# NinjaPCB_ver2_2.net
KiCad netlist of a schematic drawn in EAGLE
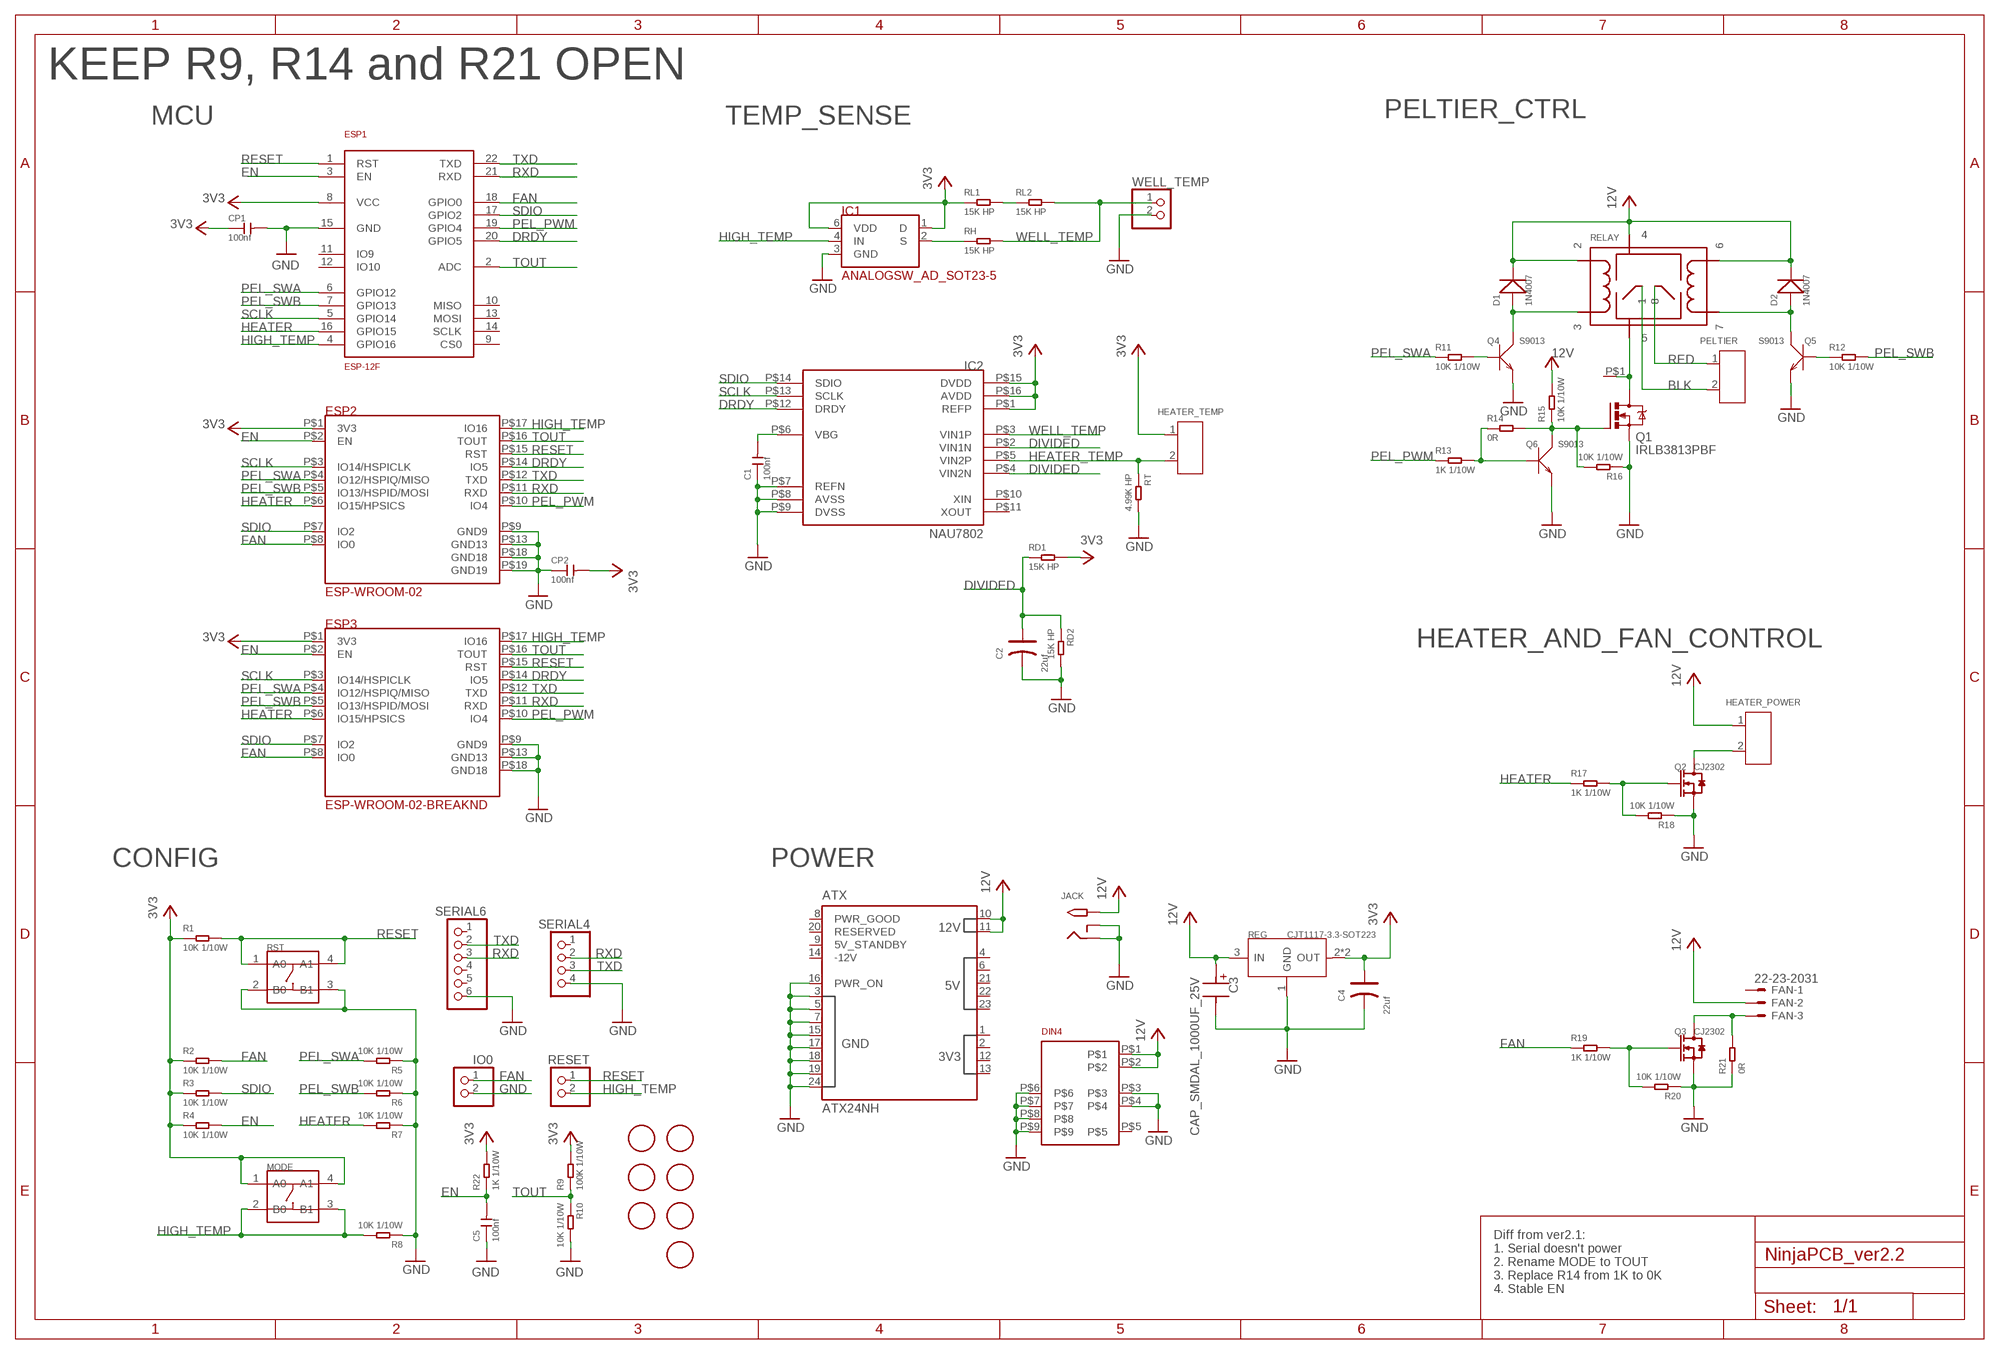
[diagram p0: schematic, sheet 1]

(export (version "E")
  (design (tool "Eeschema 10.0.6"))
  (components
    (comp (ref "ATX")
      (value "ATX24NH")
      (footprint "eagle-import:ATX24")
      (libsource (lib "eagle-import") (part "ATX24NH"))
    )
    (comp (ref "C1")
      (value "100nf")
      (footprint "eagle-import:C0603")
      (fields (field (name "MPN") "CC0603KRX7R9BB104"))
      (libsource (lib "eagle-import") (part "CERAMIC-100NF-50V-10%-X7R(0603)"))
    )
    (comp (ref "C2")
      (value "22uf")
      (footprint "eagle-import:AVX-B")
      (fields (field (name "MPN") "TAJB226*016#NJ"))
      (libsource (lib "eagle-import") (part "TANTALUM-SMD-22UF-16V(AVX-B)"))
    )
    (comp (ref "C3")
      (value "CAP_SMDAL_1000UF_25V")
      (footprint "eagle-import:CAP_SMD_AL_D125")
      (libsource (lib "eagle-import") (part "CAP_SMDAL_1000UF_25V"))
    )
    (comp (ref "C4")
      (value "22uf")
      (footprint "eagle-import:AVX-B")
      (fields (field (name "MPN") "TAJB226*016#NJ"))
      (libsource (lib "eagle-import") (part "TANTALUM-SMD-22UF-16V(AVX-B)"))
    )
    (comp (ref "C5")
      (value "100nf")
      (footprint "eagle-import:C0603")
      (fields (field (name "MPN") "CC0603KRX7R9BB104"))
      (libsource (lib "eagle-import") (part "CERAMIC-100NF-50V-10%-X7R(0603)"))
    )
    (comp (ref "CP1")
      (value "100nf")
      (footprint "eagle-import:C0603")
      (fields (field (name "MPN") "CC0603KRX7R9BB104"))
      (libsource (lib "eagle-import") (part "CERAMIC-100NF-50V-10%-X7R(0603)"))
    )
    (comp (ref "CP2")
      (value "100nf")
      (footprint "eagle-import:C0603")
      (fields (field (name "MPN") "CC0603KRX7R9BB104"))
      (libsource (lib "eagle-import") (part "CERAMIC-100NF-50V-10%-X7R(0603)"))
    )
    (comp (ref "D1")
      (value "1N4007")
      (footprint "eagle-import:DO-214AC")
      (libsource (lib "eagle-import") (part "DIODE-GEN-PURPOSE-1KV-1A(DO-214AC)"))
    )
    (comp (ref "D2")
      (value "1N4007")
      (footprint "eagle-import:DO-214AC")
      (libsource (lib "eagle-import") (part "DIODE-GEN-PURPOSE-1KV-1A(DO-214AC)"))
    )
    (comp (ref "DIN4")
      (value "DIN4")
      (footprint "eagle-import:DIN4")
      (libsource (lib "eagle-import") (part "DIN4"))
    )
    (comp (ref "ESP1")
      (value "ESP-12F")
      (footprint "eagle-import:ESP-12F")
      (libsource (lib "eagle-import") (part "ESP-12F"))
    )
    (comp (ref "ESP2")
      (value "ESP-WROOM-02")
      (footprint "eagle-import:ESP-WROOM-02")
      (libsource (lib "eagle-import") (part "ESP-WROOM-02"))
    )
    (comp (ref "ESP3")
      (value "ESP-WROOM-02-BREAKND")
      (footprint "eagle-import:ESP-WROOM-02-BREAK-NODETAIL")
      (libsource (lib "eagle-import") (part "ESP-WROOM-02-BREAKND"))
    )
    (comp (ref "FAN")
      (value "22-23-2031")
      (footprint "eagle-import:22-23-2031")
      (fields (field (name "MF") "MOLEX"))
      (libsource (lib "eagle-import") (part "22-23-2031"))
    )
    (comp (ref "HEATER_POWER")
      (value "SCREW-TERMINAL-GREEN(2P-3.5)")
      (footprint "eagle-import:H2-3.5-7.0X7.0MM")
      (libsource (lib "eagle-import") (part "SCREW-TERMINAL-GREEN(2P-3.5)"))
    )
    (comp (ref "HEATER_TEMP")
      (value "SCREW-TERMINAL-GREEN(2P-3.5)")
      (footprint "eagle-import:H2-3.5-7.0X7.0MM")
      (libsource (lib "eagle-import") (part "SCREW-TERMINAL-GREEN(2P-3.5)"))
    )
    (comp (ref "HEATSINK")
      (value "HEAT111PB015")
      (footprint "eagle-import:HEAT11PB015")
      (libsource (lib "eagle-import") (part "HEAT111PB015"))
    )
    (comp (ref "IC1")
      (value "ANALOGSW_AD_SOT23-5")
      (footprint "eagle-import:SOT23-5")
      (libsource (lib "eagle-import") (part "ANALOGSW_AD_SOT23-5"))
    )
    (comp (ref "IC2")
      (value "NAU7802")
      (footprint "eagle-import:SOP-16")
      (libsource (lib "eagle-import") (part "NAU7802"))
    )
    (comp (ref "IO0")
      (value "PINHD-1X2")
      (footprint "eagle-import:1X02")
      (libsource (lib "eagle-import") (part "PINHD-1X2"))
    )
    (comp (ref "JACK")
      (value "2.1MMJACKTHM-NOOUT")
      (footprint "eagle-import:PJ-102A-NOOUT")
      (libsource (lib "eagle-import") (part "2.1MMJACKTHM-NOOUT"))
    )
    (comp (ref "MODE")
      (value "DIP-SWITCH-TACTILE-SPST-NO/TS-1109(4P-D6.0MM)'TS-1109'")
      (footprint "eagle-import:SW4-6.0X6.0X5.0MM")
      (libsource (lib "eagle-import") (part "DIP-SWITCH-TACTILE-SPST-NO/TS-1109(4P-D6.0MM)'TS-1109'"))
    )
    (comp (ref "PELTIER")
      (value "SCREW-TERMINAL-GREEN(2P-3.5)")
      (footprint "eagle-import:H2-3.5-7.0X7.0MM")
      (libsource (lib "eagle-import") (part "SCREW-TERMINAL-GREEN(2P-3.5)"))
    )
    (comp (ref "Q1")
      (value "IRLB3813PBF")
      (footprint "eagle-import:TO220BV")
      (libsource (lib "eagle-import") (part "IRF520"))
    )
    (comp (ref "Q2")
      (value "CJ2302")
      (footprint "eagle-import:SOT-23")
      (libsource (lib "eagle-import") (part "SMD-MOSFET-N-CH-20V-2.1A-CJ2302(SOT-23)"))
    )
    (comp (ref "Q3")
      (value "CJ2302")
      (footprint "eagle-import:SOT-23")
      (libsource (lib "eagle-import") (part "SMD-MOSFET-N-CH-20V-2.1A-CJ2302(SOT-23)"))
    )
    (comp (ref "Q4")
      (value "S9013")
      (footprint "eagle-import:SOT-23")
      (libsource (lib "eagle-import") (part "SMD-TRANSISTORS-NPN-25V-500MA-S9013(SOT-23)"))
    )
    (comp (ref "Q5")
      (value "S9013")
      (footprint "eagle-import:SOT-23")
      (libsource (lib "eagle-import") (part "SMD-TRANSISTORS-NPN-25V-500MA-S9013(SOT-23)"))
    )
    (comp (ref "Q6")
      (value "S9013")
      (footprint "eagle-import:SOT-23")
      (libsource (lib "eagle-import") (part "SMD-TRANSISTORS-NPN-25V-500MA-S9013(SOT-23)"))
    )
    (comp (ref "R1")
      (value "10K 1/10W")
      (footprint "eagle-import:R0603")
      (fields (field (name "MPN") "RC0603JR-0710KL"))
      (libsource (lib "eagle-import") (part "SMD-RES-10K-5%-1/10W(0603)"))
    )
    (comp (ref "R2")
      (value "10K 1/10W")
      (footprint "eagle-import:R0603")
      (fields (field (name "MPN") "RC0603JR-0710KL"))
      (libsource (lib "eagle-import") (part "SMD-RES-10K-5%-1/10W(0603)"))
    )
    (comp (ref "R3")
      (value "10K 1/10W")
      (footprint "eagle-import:R0603")
      (fields (field (name "MPN") "RC0603JR-0710KL"))
      (libsource (lib "eagle-import") (part "SMD-RES-10K-5%-1/10W(0603)"))
    )
    (comp (ref "R4")
      (value "10K 1/10W")
      (footprint "eagle-import:R0603")
      (fields (field (name "MPN") "RC0603JR-0710KL"))
      (libsource (lib "eagle-import") (part "SMD-RES-10K-5%-1/10W(0603)"))
    )
    (comp (ref "R5")
      (value "10K 1/10W")
      (footprint "eagle-import:R0603")
      (fields (field (name "MPN") "RC0603JR-0710KL"))
      (libsource (lib "eagle-import") (part "SMD-RES-10K-5%-1/10W(0603)"))
    )
    (comp (ref "R6")
      (value "10K 1/10W")
      (footprint "eagle-import:R0603")
      (fields (field (name "MPN") "RC0603JR-0710KL"))
      (libsource (lib "eagle-import") (part "SMD-RES-10K-5%-1/10W(0603)"))
    )
    (comp (ref "R7")
      (value "10K 1/10W")
      (footprint "eagle-import:R0603")
      (fields (field (name "MPN") "RC0603JR-0710KL"))
      (libsource (lib "eagle-import") (part "SMD-RES-10K-5%-1/10W(0603)"))
    )
    (comp (ref "R8")
      (value "10K 1/10W")
      (footprint "eagle-import:R0603")
      (fields (field (name "MPN") "RC0603JR-0710KL"))
      (libsource (lib "eagle-import") (part "SMD-RES-10K-5%-1/10W(0603)"))
    )
    (comp (ref "R9")
      (value "100K 1/10W")
      (footprint "eagle-import:R0603")
      (fields (field (name "MPN") "RC0603JR-07100KL"))
      (libsource (lib "eagle-import") (part "SMD-RES-100K-5%-1/10W(0603)"))
    )
    (comp (ref "R10")
      (value "10K 1/10W")
      (footprint "eagle-import:R0603")
      (fields (field (name "MPN") "RC0603JR-0710KL"))
      (libsource (lib "eagle-import") (part "SMD-RES-10K-5%-1/10W(0603)"))
    )
    (comp (ref "R11")
      (value "10K 1/10W")
      (footprint "eagle-import:R0603")
      (fields (field (name "MPN") "RC0603JR-0710KL"))
      (libsource (lib "eagle-import") (part "SMD-RES-10K-5%-1/10W(0603)"))
    )
    (comp (ref "R12")
      (value "10K 1/10W")
      (footprint "eagle-import:R0603")
      (fields (field (name "MPN") "RC0603JR-0710KL"))
      (libsource (lib "eagle-import") (part "SMD-RES-10K-5%-1/10W(0603)"))
    )
    (comp (ref "R13")
      (value "1K 1/10W")
      (footprint "eagle-import:R0603")
      (fields (field (name "MPN") "RC0603JR-071KL"))
      (libsource (lib "eagle-import") (part "SMD-RES-1K-5%-1/10W(0603)"))
    )
    (comp (ref "R14")
      (value "0R")
      (footprint "eagle-import:R0603")
      (fields (field (name "MPN") "RC0603JR-070RL"))
      (libsource (lib "eagle-import") (part "SMD-RES-0R-5%-1/10W(0603)"))
    )
    (comp (ref "R15")
      (value "10K 1/10W")
      (footprint "eagle-import:R0603")
      (fields (field (name "MPN") "RC0603JR-0710KL"))
      (libsource (lib "eagle-import") (part "SMD-RES-10K-5%-1/10W(0603)"))
    )
    (comp (ref "R16")
      (value "10K 1/10W")
      (footprint "eagle-import:R0603")
      (fields (field (name "MPN") "RC0603JR-0710KL"))
      (libsource (lib "eagle-import") (part "SMD-RES-10K-5%-1/10W(0603)"))
    )
    (comp (ref "R17")
      (value "1K 1/10W")
      (footprint "eagle-import:R0603")
      (fields (field (name "MPN") "RC0603JR-071KL"))
      (libsource (lib "eagle-import") (part "SMD-RES-1K-5%-1/10W(0603)"))
    )
    (comp (ref "R18")
      (value "10K 1/10W")
      (footprint "eagle-import:R0603")
      (fields (field (name "MPN") "RC0603JR-0710KL"))
      (libsource (lib "eagle-import") (part "SMD-RES-10K-5%-1/10W(0603)"))
    )
    (comp (ref "R19")
      (value "1K 1/10W")
      (footprint "eagle-import:R0603")
      (fields (field (name "MPN") "RC0603JR-071KL"))
      (libsource (lib "eagle-import") (part "SMD-RES-1K-5%-1/10W(0603)"))
    )
    (comp (ref "R20")
      (value "10K 1/10W")
      (footprint "eagle-import:R0603")
      (fields (field (name "MPN") "RC0603JR-0710KL"))
      (libsource (lib "eagle-import") (part "SMD-RES-10K-5%-1/10W(0603)"))
    )
    (comp (ref "R21")
      (value "0R")
      (footprint "eagle-import:R0603")
      (fields (field (name "MPN") "RC0603JR-070RL"))
      (libsource (lib "eagle-import") (part "SMD-RES-0R-5%-1/10W(0603)"))
    )
    (comp (ref "R22")
      (value "1K 1/10W")
      (footprint "eagle-import:R0603")
      (fields (field (name "MPN") "RC0603JR-071KL"))
      (libsource (lib "eagle-import") (part "SMD-RES-1K-5%-1/10W(0603)"))
    )
    (comp (ref "RD1")
      (value "15K HP")
      (footprint "eagle-import:R0603")
      (libsource (lib "eagle-import") (part "R0603"))
    )
    (comp (ref "RD2")
      (value "15K HP")
      (footprint "eagle-import:R0603")
      (libsource (lib "eagle-import") (part "R0603"))
    )
    (comp (ref "REG")
      (value "CJT1117-3.3-SOT223")
      (footprint "eagle-import:SOT-223")
      (fields (field (name "MPN") "CJT1117-3.3"))
      (libsource (lib "eagle-import") (part "PMIC-CJT1117-3.3(SOT223)"))
    )
    (comp (ref "RELAY")
      (value "NEC-RELAY2EP2")
      (footprint "eagle-import:NEC-EP2")
      (libsource (lib "eagle-import") (part "NEC-RELAY2EP2"))
    )
    (comp (ref "RESET")
      (value "PINHD-1X2")
      (footprint "eagle-import:1X02")
      (libsource (lib "eagle-import") (part "PINHD-1X2"))
    )
    (comp (ref "RH")
      (value "15K HP")
      (footprint "eagle-import:R0603")
      (libsource (lib "eagle-import") (part "R0603"))
    )
    (comp (ref "RL1")
      (value "15K HP")
      (footprint "eagle-import:R0603")
      (libsource (lib "eagle-import") (part "R0603"))
    )
    (comp (ref "RL2")
      (value "15K HP")
      (footprint "eagle-import:R0603")
      (libsource (lib "eagle-import") (part "R0603"))
    )
    (comp (ref "RST")
      (value "DIP-SWITCH-TACTILE-SPST-NO/TS-1109(4P-D6.0MM)'TS-1109'")
      (footprint "eagle-import:SW4-6.0X6.0X5.0MM")
      (libsource (lib "eagle-import") (part "DIP-SWITCH-TACTILE-SPST-NO/TS-1109(4P-D6.0MM)'TS-1109'"))
    )
    (comp (ref "RT")
      (value "4.99K HP")
      (footprint "eagle-import:R0603")
      (fields (field (name "MPN") "RC0603FR-072KL"))
      (libsource (lib "eagle-import") (part "SMD-RES-2K-1%-1/10W(0603)"))
    )
    (comp (ref "SERIAL4")
      (value "PINHD-1X4")
      (footprint "eagle-import:1X04")
      (libsource (lib "eagle-import") (part "PINHD-1X4"))
    )
    (comp (ref "SERIAL6")
      (value "PINHD-1X6")
      (footprint "eagle-import:1X06")
      (libsource (lib "eagle-import") (part "PINHD-1X6"))
    )
    (comp (ref "U$3")
      (value "FIDUCIAL")
      (footprint "eagle-import:FIDUCIAL_1MM")
      (libsource (lib "eagle-import") (part "FIDUCIAL"))
    )
    (comp (ref "U$4")
      (value "FIDUCIAL")
      (footprint "eagle-import:FIDUCIAL_1MM")
      (libsource (lib "eagle-import") (part "FIDUCIAL"))
    )
    (comp (ref "U$5")
      (value "FIDUCIAL")
      (footprint "eagle-import:FIDUCIAL_1MM")
      (libsource (lib "eagle-import") (part "FIDUCIAL"))
    )
    (comp (ref "U$7")
      (value "FIDUCIAL")
      (footprint "eagle-import:FIDUCIAL_1MM")
      (libsource (lib "eagle-import") (part "FIDUCIAL"))
    )
    (comp (ref "U$8")
      (value "FIDUCIAL")
      (footprint "eagle-import:FIDUCIAL_1MM")
      (libsource (lib "eagle-import") (part "FIDUCIAL"))
    )
    (comp (ref "U$9")
      (value "FIDUCIAL")
      (footprint "eagle-import:FIDUCIAL_1MM")
      (libsource (lib "eagle-import") (part "FIDUCIAL"))
    )
    (comp (ref "U$10")
      (value "FIDUCIAL")
      (footprint "eagle-import:FIDUCIAL_1MM")
      (libsource (lib "eagle-import") (part "FIDUCIAL"))
    )
    (comp (ref "WELL_TEMP")
      (value "PINHD-1X2/90")
      (footprint "eagle-import:1X02_90")
      (libsource (lib "eagle-import") (part "PINHD-1X2/90"))
    )
  )
  (nets
    (net (code "1") (name "/BLK") (class "Default")
      (node (ref "PELTIER") (pin "2") (pinfunction "2_2") (pintype "bidirectional"))
      (node (ref "RELAY") (pin "P$1") (pinfunction "1_P$1") (pintype "bidirectional"))
    )
    (net (code "2") (name "/DIVIDED") (class "Default")
      (node (ref "C2") (pin "+") (pinfunction "+_+") (pintype "passive"))
      (node (ref "IC2") (pin "P$2") (pinfunction "VIN1N_P$2") (pintype "bidirectional"))
      (node (ref "IC2") (pin "P$4") (pinfunction "VIN2N_P$4") (pintype "bidirectional"))
      (node (ref "RD1") (pin "1") (pinfunction "1_1") (pintype "passive"))
      (node (ref "RD2") (pin "1") (pinfunction "1_1") (pintype "passive"))
    )
    (net (code "3") (name "/DRDY") (class "Default")
      (node (ref "ESP1") (pin "20") (pinfunction "GPIO5_20") (pintype "bidirectional"))
      (node (ref "ESP2") (pin "P$14") (pinfunction "IO5_P$14") (pintype "bidirectional"))
      (node (ref "ESP3") (pin "P$14") (pinfunction "IO5_P$14") (pintype "bidirectional"))
      (node (ref "IC2") (pin "P$12") (pinfunction "DRDY_P$12") (pintype "bidirectional"))
    )
    (net (code "4") (name "/EN") (class "Default")
      (node (ref "C5") (pin "2") (pinfunction "2_2") (pintype "passive"))
      (node (ref "ESP1") (pin "3") (pinfunction "EN_3") (pintype "bidirectional"))
      (node (ref "ESP2") (pin "P$2") (pinfunction "EN_P$2") (pintype "bidirectional"))
      (node (ref "ESP3") (pin "P$2") (pinfunction "EN_P$2") (pintype "bidirectional"))
      (node (ref "R22") (pin "1") (pinfunction "1_1") (pintype "passive"))
      (node (ref "R4") (pin "2") (pinfunction "2_2") (pintype "passive"))
    )
    (net (code "5") (name "/FAN") (class "Default")
      (node (ref "ESP1") (pin "18") (pinfunction "GPIO0_18") (pintype "bidirectional"))
      (node (ref "ESP2") (pin "P$8") (pinfunction "IO0_P$8") (pintype "bidirectional"))
      (node (ref "ESP3") (pin "P$8") (pinfunction "IO0_P$8") (pintype "bidirectional"))
      (node (ref "IO0") (pin "1") (pinfunction "1_1") (pintype "passive"))
      (node (ref "R19") (pin "1") (pinfunction "1_1") (pintype "passive"))
      (node (ref "R2") (pin "2") (pinfunction "2_2") (pintype "passive"))
    )
    (net (code "6") (name "/HEATER") (class "Default")
      (node (ref "ESP1") (pin "16") (pinfunction "GPIO15_16") (pintype "bidirectional"))
      (node (ref "ESP2") (pin "P$6") (pinfunction "IO15/HPSICS_P$6") (pintype "bidirectional"))
      (node (ref "ESP3") (pin "P$6") (pinfunction "IO15/HPSICS_P$6") (pintype "bidirectional"))
      (node (ref "R17") (pin "1") (pinfunction "1_1") (pintype "passive"))
      (node (ref "R7") (pin "2") (pinfunction "2_2") (pintype "passive"))
    )
    (net (code "7") (name "/HEATER_TEMP") (class "Default")
      (node (ref "HEATER_TEMP") (pin "2") (pinfunction "2_2") (pintype "bidirectional"))
      (node (ref "IC2") (pin "P$5") (pinfunction "VIN2P_P$5") (pintype "bidirectional"))
      (node (ref "RT") (pin "1") (pinfunction "1_1") (pintype "passive"))
    )
    (net (code "8") (name "/HIGH_TEMP") (class "Default")
      (node (ref "ESP1") (pin "4") (pinfunction "GPIO16_4") (pintype "bidirectional"))
      (node (ref "ESP2") (pin "P$17") (pinfunction "IO16_P$17") (pintype "bidirectional"))
      (node (ref "ESP3") (pin "P$17") (pinfunction "IO16_P$17") (pintype "bidirectional"))
      (node (ref "IC1") (pin "4") (pinfunction "IN_4") (pintype "bidirectional"))
      (node (ref "MODE") (pin "2") (pinfunction "B0_2") (pintype "bidirectional"))
      (node (ref "MODE") (pin "3") (pinfunction "B1_3") (pintype "bidirectional"))
      (node (ref "R8") (pin "2") (pinfunction "2_2") (pintype "passive"))
      (node (ref "RESET") (pin "2") (pinfunction "2_2") (pintype "passive"))
    )
    (net (code "9") (name "/PEL_PWM") (class "Default")
      (node (ref "ESP1") (pin "19") (pinfunction "GPIO4_19") (pintype "bidirectional"))
      (node (ref "ESP2") (pin "P$10") (pinfunction "IO4_P$10") (pintype "bidirectional"))
      (node (ref "ESP3") (pin "P$10") (pinfunction "IO4_P$10") (pintype "bidirectional"))
      (node (ref "R13") (pin "1") (pinfunction "1_1") (pintype "passive"))
    )
    (net (code "10") (name "/PEL_SWA") (class "Default")
      (node (ref "ESP1") (pin "6") (pinfunction "GPIO12_6") (pintype "bidirectional"))
      (node (ref "ESP2") (pin "P$4") (pinfunction "IO12/HSPIQ/MISO_P$4") (pintype "bidirectional"))
      (node (ref "ESP3") (pin "P$4") (pinfunction "IO12/HSPIQ/MISO_P$4") (pintype "bidirectional"))
      (node (ref "R11") (pin "1") (pinfunction "1_1") (pintype "passive"))
      (node (ref "R5") (pin "2") (pinfunction "2_2") (pintype "passive"))
    )
    (net (code "11") (name "/PEL_SWB") (class "Default")
      (node (ref "ESP1") (pin "7") (pinfunction "GPIO13_7") (pintype "bidirectional"))
      (node (ref "ESP2") (pin "P$5") (pinfunction "IO13/HSPID/MOSI_P$5") (pintype "bidirectional"))
      (node (ref "ESP3") (pin "P$5") (pinfunction "IO13/HSPID/MOSI_P$5") (pintype "bidirectional"))
      (node (ref "R12") (pin "2") (pinfunction "2_2") (pintype "passive"))
      (node (ref "R6") (pin "2") (pinfunction "2_2") (pintype "passive"))
    )
    (net (code "12") (name "/RED") (class "Default")
      (node (ref "PELTIER") (pin "1") (pinfunction "1_1") (pintype "bidirectional"))
      (node (ref "RELAY") (pin "P$8") (pinfunction "8_P$8") (pintype "bidirectional"))
    )
    (net (code "13") (name "/RESET") (class "Default")
      (node (ref "ESP1") (pin "1") (pinfunction "RST_1") (pintype "bidirectional"))
      (node (ref "ESP2") (pin "P$15") (pinfunction "RST_P$15") (pintype "bidirectional"))
      (node (ref "ESP3") (pin "P$15") (pinfunction "RST_P$15") (pintype "bidirectional"))
      (node (ref "R1") (pin "2") (pinfunction "2_2") (pintype "passive"))
      (node (ref "RESET") (pin "1") (pinfunction "1_1") (pintype "passive"))
      (node (ref "RST") (pin "1") (pinfunction "A0_1") (pintype "bidirectional"))
      (node (ref "RST") (pin "4") (pinfunction "A1_4") (pintype "bidirectional"))
    )
    (net (code "14") (name "/RXD") (class "Default")
      (node (ref "ESP1") (pin "21") (pinfunction "RXD_21") (pintype "bidirectional"))
      (node (ref "ESP2") (pin "P$11") (pinfunction "RXD_P$11") (pintype "bidirectional"))
      (node (ref "ESP3") (pin "P$11") (pinfunction "RXD_P$11") (pintype "bidirectional"))
      (node (ref "SERIAL4") (pin "2") (pinfunction "2_2") (pintype "passive"))
      (node (ref "SERIAL6") (pin "3") (pinfunction "3_3") (pintype "passive"))
    )
    (net (code "15") (name "/SCLK") (class "Default")
      (node (ref "ESP1") (pin "5") (pinfunction "GPIO14_5") (pintype "bidirectional"))
      (node (ref "ESP2") (pin "P$3") (pinfunction "IO14/HSPICLK_P$3") (pintype "bidirectional"))
      (node (ref "ESP3") (pin "P$3") (pinfunction "IO14/HSPICLK_P$3") (pintype "bidirectional"))
      (node (ref "IC2") (pin "P$13") (pinfunction "SCLK_P$13") (pintype "bidirectional"))
    )
    (net (code "16") (name "/SDIO") (class "Default")
      (node (ref "ESP1") (pin "17") (pinfunction "GPIO2_17") (pintype "bidirectional"))
      (node (ref "ESP2") (pin "P$7") (pinfunction "IO2_P$7") (pintype "bidirectional"))
      (node (ref "ESP3") (pin "P$7") (pinfunction "IO2_P$7") (pintype "bidirectional"))
      (node (ref "IC2") (pin "P$14") (pinfunction "SDIO_P$14") (pintype "bidirectional"))
      (node (ref "R3") (pin "2") (pinfunction "2_2") (pintype "passive"))
    )
    (net (code "17") (name "/TOUT") (class "Default")
      (node (ref "ESP1") (pin "2") (pinfunction "ADC_2") (pintype "bidirectional"))
      (node (ref "ESP2") (pin "P$16") (pinfunction "TOUT_P$16") (pintype "bidirectional"))
      (node (ref "ESP3") (pin "P$16") (pinfunction "TOUT_P$16") (pintype "bidirectional"))
      (node (ref "R10") (pin "1") (pinfunction "1_1") (pintype "passive"))
      (node (ref "R9") (pin "1") (pinfunction "1_1") (pintype "passive"))
    )
    (net (code "18") (name "/TXD") (class "Default")
      (node (ref "ESP1") (pin "22") (pinfunction "TXD_22") (pintype "bidirectional"))
      (node (ref "ESP2") (pin "P$12") (pinfunction "TXD_P$12") (pintype "bidirectional"))
      (node (ref "ESP3") (pin "P$12") (pinfunction "TXD_P$12") (pintype "bidirectional"))
      (node (ref "SERIAL4") (pin "3") (pinfunction "3_3") (pintype "passive"))
      (node (ref "SERIAL6") (pin "2") (pinfunction "2_2") (pintype "passive"))
    )
    (net (code "19") (name "/WELL_TEMP") (class "Default")
      (node (ref "IC2") (pin "P$3") (pinfunction "VIN1P_P$3") (pintype "bidirectional"))
      (node (ref "RH") (pin "2") (pinfunction "2_2") (pintype "passive"))
      (node (ref "RL2") (pin "2") (pinfunction "2_2") (pintype "passive"))
      (node (ref "WELL_TEMP") (pin "1") (pinfunction "1_1") (pintype "passive"))
    )
    (net (code "20") (name "3V3") (class "Default")
      (node (ref "C4") (pin "+") (pinfunction "+_+") (pintype "passive"))
      (node (ref "CP1") (pin "1") (pinfunction "1_1") (pintype "passive"))
      (node (ref "CP2") (pin "2") (pinfunction "2_2") (pintype "passive"))
      (node (ref "ESP1") (pin "8") (pinfunction "VCC_8") (pintype "bidirectional"))
      (node (ref "ESP2") (pin "P$1") (pinfunction "3V3_P$1") (pintype "bidirectional"))
      (node (ref "ESP3") (pin "P$1") (pinfunction "3V3_P$1") (pintype "bidirectional"))
      (node (ref "HEATER_TEMP") (pin "1") (pinfunction "1_1") (pintype "bidirectional"))
      (node (ref "IC1") (pin "1") (pinfunction "D_1") (pintype "bidirectional"))
      (node (ref "IC1") (pin "6") (pinfunction "VDD_6") (pintype "bidirectional"))
      (node (ref "IC2") (pin "P$1") (pinfunction "REFP_P$1") (pintype "bidirectional"))
      (node (ref "IC2") (pin "P$15") (pinfunction "DVDD_P$15") (pintype "bidirectional"))
      (node (ref "IC2") (pin "P$16") (pinfunction "AVDD_P$16") (pintype "bidirectional"))
      (node (ref "MODE") (pin "1") (pinfunction "A0_1") (pintype "bidirectional"))
      (node (ref "MODE") (pin "4") (pinfunction "A1_4") (pintype "bidirectional"))
      (node (ref "R1") (pin "1") (pinfunction "1_1") (pintype "passive"))
      (node (ref "R2") (pin "1") (pinfunction "1_1") (pintype "passive"))
      (node (ref "R22") (pin "2") (pinfunction "2_2") (pintype "passive"))
      (node (ref "R3") (pin "1") (pinfunction "1_1") (pintype "passive"))
      (node (ref "R4") (pin "1") (pinfunction "1_1") (pintype "passive"))
      (node (ref "R9") (pin "2") (pinfunction "2_2") (pintype "passive"))
      (node (ref "RD1") (pin "2") (pinfunction "2_2") (pintype "passive"))
      (node (ref "REG") (pin "2") (pinfunction "OUT_2") (pintype "bidirectional"))
      (node (ref "REG") (pin "TER") (pinfunction "OUT_TER") (pintype "bidirectional"))
      (node (ref "RL1") (pin "1") (pinfunction "1_1") (pintype "passive"))
    )
    (net (code "21") (name "12V") (class "Default")
      (node (ref "ATX") (pin "10") (pinfunction "12V_10_10") (pintype "bidirectional"))
      (node (ref "ATX") (pin "11") (pinfunction "12V_11_11") (pintype "bidirectional"))
      (node (ref "C3") (pin "P$P") (pinfunction "P$P_P$P") (pintype "passive"))
      (node (ref "D1") (pin "2") (pinfunction "-_2") (pintype "passive"))
      (node (ref "D2") (pin "2") (pinfunction "-_2") (pintype "passive"))
      (node (ref "DIN4") (pin "P$1") (pinfunction "P$1_P$1") (pintype "bidirectional"))
      (node (ref "DIN4") (pin "P$2") (pinfunction "P$2_P$2") (pintype "bidirectional"))
      (node (ref "FAN") (pin "2") (pinfunction "S_2") (pintype "passive"))
      (node (ref "HEATER_POWER") (pin "1") (pinfunction "1_1") (pintype "bidirectional"))
      (node (ref "JACK") (pin "TIP") (pinfunction "TIP_TIP") (pintype "bidirectional"))
      (node (ref "R15") (pin "2") (pinfunction "2_2") (pintype "passive"))
      (node (ref "REG") (pin "3") (pinfunction "IN_3") (pintype "bidirectional"))
      (node (ref "RELAY") (pin "P$2") (pinfunction "2_P$2") (pintype "bidirectional"))
      (node (ref "RELAY") (pin "P$4") (pinfunction "4_P$4") (pintype "bidirectional"))
      (node (ref "RELAY") (pin "P$6") (pinfunction "6_P$6") (pintype "bidirectional"))
    )
    (net (code "22") (name "GND") (class "Default")
      (node (ref "ATX") (pin "15") (pinfunction "GND15_15") (pintype "bidirectional"))
      (node (ref "ATX") (pin "16") (pinfunction "PWR_ON_16") (pintype "bidirectional"))
      (node (ref "ATX") (pin "17") (pinfunction "GND17_17") (pintype "bidirectional"))
      (node (ref "ATX") (pin "18") (pinfunction "GND18_18") (pintype "bidirectional"))
      (node (ref "ATX") (pin "19") (pinfunction "GND19_19") (pintype "bidirectional"))
      (node (ref "ATX") (pin "24") (pinfunction "GND24_24") (pintype "bidirectional"))
      (node (ref "ATX") (pin "3") (pinfunction "GND3_3") (pintype "bidirectional"))
      (node (ref "ATX") (pin "5") (pinfunction "GND5_5") (pintype "bidirectional"))
      (node (ref "ATX") (pin "7") (pinfunction "GND7_7") (pintype "bidirectional"))
      (node (ref "C1") (pin "1") (pinfunction "1_1") (pintype "passive"))
      (node (ref "C2") (pin "-") (pinfunction "-_-") (pintype "passive"))
      (node (ref "C3") (pin "P$M") (pinfunction "P$M_P$M") (pintype "passive"))
      (node (ref "C4") (pin "-") (pinfunction "-_-") (pintype "passive"))
      (node (ref "C5") (pin "1") (pinfunction "1_1") (pintype "passive"))
      (node (ref "CP1") (pin "2") (pinfunction "2_2") (pintype "passive"))
      (node (ref "CP2") (pin "1") (pinfunction "1_1") (pintype "passive"))
      (node (ref "DIN4") (pin "P$3") (pinfunction "P$3_P$3") (pintype "bidirectional"))
      (node (ref "DIN4") (pin "P$4") (pinfunction "P$4_P$4") (pintype "bidirectional"))
      (node (ref "DIN4") (pin "P$6") (pinfunction "P$6_P$6") (pintype "bidirectional"))
      (node (ref "DIN4") (pin "P$7") (pinfunction "P$7_P$7") (pintype "bidirectional"))
      (node (ref "DIN4") (pin "P$8") (pinfunction "P$8_P$8") (pintype "bidirectional"))
      (node (ref "DIN4") (pin "P$9") (pinfunction "P$9_P$9") (pintype "bidirectional"))
      (node (ref "ESP1") (pin "15") (pinfunction "GND_15") (pintype "bidirectional"))
      (node (ref "ESP2") (pin "P$13") (pinfunction "GND13_P$13") (pintype "bidirectional"))
      (node (ref "ESP2") (pin "P$18") (pinfunction "GND18_P$18") (pintype "bidirectional"))
      (node (ref "ESP2") (pin "P$19") (pinfunction "GND19_P$19") (pintype "bidirectional"))
      (node (ref "ESP2") (pin "P$9") (pinfunction "GND9_P$9") (pintype "bidirectional"))
      (node (ref "ESP3") (pin "P$13") (pinfunction "GND13_P$13") (pintype "bidirectional"))
      (node (ref "ESP3") (pin "P$18") (pinfunction "GND18_P$18") (pintype "bidirectional"))
      (node (ref "ESP3") (pin "P$9") (pinfunction "GND9_P$9") (pintype "bidirectional"))
      (node (ref "IC1") (pin "3") (pinfunction "GND_3") (pintype "bidirectional"))
      (node (ref "IC2") (pin "P$7") (pinfunction "REFN_P$7") (pintype "bidirectional"))
      (node (ref "IC2") (pin "P$8") (pinfunction "AVSS_P$8") (pintype "bidirectional"))
      (node (ref "IC2") (pin "P$9") (pinfunction "DVSS_P$9") (pintype "bidirectional"))
      (node (ref "IO0") (pin "2") (pinfunction "2_2") (pintype "passive"))
      (node (ref "JACK") (pin "RING") (pinfunction "RING_RING") (pintype "bidirectional"))
      (node (ref "JACK") (pin "RING_SW") (pinfunction "RING_SW_RING_SW") (pintype "bidirectional"))
      (node (ref "Q1") (pin "S") (pinfunction "S_S") (pintype "passive"))
      (node (ref "Q2") (pin "2") (pinfunction "S_2") (pintype "passive"))
      (node (ref "Q3") (pin "2") (pinfunction "S_2") (pintype "passive"))
      (node (ref "Q4") (pin "2") (pinfunction "E_2") (pintype "passive"))
      (node (ref "Q5") (pin "2") (pinfunction "E_2") (pintype "passive"))
      (node (ref "Q6") (pin "2") (pinfunction "E_2") (pintype "passive"))
      (node (ref "R10") (pin "2") (pinfunction "2_2") (pintype "passive"))
      (node (ref "R16") (pin "1") (pinfunction "1_1") (pintype "passive"))
      (node (ref "R18") (pin "1") (pinfunction "1_1") (pintype "passive"))
      (node (ref "R20") (pin "1") (pinfunction "1_1") (pintype "passive"))
      (node (ref "R21") (pin "1") (pinfunction "1_1") (pintype "passive"))
      (node (ref "R5") (pin "1") (pinfunction "1_1") (pintype "passive"))
      (node (ref "R6") (pin "1") (pinfunction "1_1") (pintype "passive"))
      (node (ref "R7") (pin "1") (pinfunction "1_1") (pintype "passive"))
      (node (ref "R8") (pin "1") (pinfunction "1_1") (pintype "passive"))
      (node (ref "RD2") (pin "2") (pinfunction "2_2") (pintype "passive"))
      (node (ref "REG") (pin "1") (pinfunction "GND_1") (pintype "bidirectional"))
      (node (ref "RST") (pin "2") (pinfunction "B0_2") (pintype "bidirectional"))
      (node (ref "RST") (pin "3") (pinfunction "B1_3") (pintype "bidirectional"))
      (node (ref "RT") (pin "2") (pinfunction "2_2") (pintype "passive"))
      (node (ref "SERIAL4") (pin "4") (pinfunction "4_4") (pintype "passive"))
      (node (ref "SERIAL6") (pin "6") (pinfunction "6_6") (pintype "passive"))
      (node (ref "WELL_TEMP") (pin "2") (pinfunction "2_2") (pintype "passive"))
    )
    (net (code "23") (name "Net-(D1-+)") (class "Default")
      (node (ref "D1") (pin "1") (pinfunction "+_1") (pintype "passive"))
      (node (ref "Q4") (pin "3") (pinfunction "C_3") (pintype "passive"))
      (node (ref "RELAY") (pin "P$3") (pinfunction "3_P$3") (pintype "bidirectional"))
    )
    (net (code "24") (name "Net-(D2-+)") (class "Default")
      (node (ref "D2") (pin "1") (pinfunction "+_1") (pintype "passive"))
      (node (ref "Q5") (pin "3") (pinfunction "C_3") (pintype "passive"))
      (node (ref "RELAY") (pin "P$7") (pinfunction "7_P$7") (pintype "bidirectional"))
    )
    (net (code "25") (name "Net-(FANC-S)") (class "Default")
      (node (ref "FAN") (pin "3") (pinfunction "S_3") (pintype "passive"))
      (node (ref "Q3") (pin "3") (pinfunction "D_3") (pintype "passive"))
      (node (ref "R21") (pin "2") (pinfunction "2_2") (pintype "passive"))
    )
    (net (code "26") (name "Net-(IC1-S)") (class "Default")
      (node (ref "IC1") (pin "2") (pinfunction "S_2") (pintype "bidirectional"))
      (node (ref "RH") (pin "1") (pinfunction "1_1") (pintype "passive"))
    )
    (net (code "27") (name "Net-(IC2-VBG)") (class "Default")
      (node (ref "C1") (pin "2") (pinfunction "2_2") (pintype "passive"))
      (node (ref "IC2") (pin "P$6") (pinfunction "VBG_P$6") (pintype "bidirectional"))
    )
    (net (code "28") (name "Net-(Q2-D)") (class "Default")
      (node (ref "HEATER_POWER") (pin "2") (pinfunction "2_2") (pintype "bidirectional"))
      (node (ref "Q2") (pin "3") (pinfunction "D_3") (pintype "passive"))
    )
    (net (code "29") (name "Net-(Q2-G)") (class "Default")
      (node (ref "Q2") (pin "1") (pinfunction "G_1") (pintype "passive"))
      (node (ref "R17") (pin "2") (pinfunction "2_2") (pintype "passive"))
      (node (ref "R18") (pin "2") (pinfunction "2_2") (pintype "passive"))
    )
    (net (code "30") (name "Net-(Q3-G)") (class "Default")
      (node (ref "Q3") (pin "1") (pinfunction "G_1") (pintype "passive"))
      (node (ref "R19") (pin "2") (pinfunction "2_2") (pintype "passive"))
      (node (ref "R20") (pin "2") (pinfunction "2_2") (pintype "passive"))
    )
    (net (code "31") (name "Net-(Q4-B)") (class "Default")
      (node (ref "Q4") (pin "1") (pinfunction "B_1") (pintype "passive"))
      (node (ref "R11") (pin "2") (pinfunction "2_2") (pintype "passive"))
    )
    (net (code "32") (name "Net-(Q5-B)") (class "Default")
      (node (ref "Q5") (pin "1") (pinfunction "B_1") (pintype "passive"))
      (node (ref "R12") (pin "1") (pinfunction "1_1") (pintype "passive"))
    )
    (net (code "33") (name "Net-(Q6-B)") (class "Default")
      (node (ref "Q6") (pin "1") (pinfunction "B_1") (pintype "passive"))
      (node (ref "R13") (pin "2") (pinfunction "2_2") (pintype "passive"))
      (node (ref "R14") (pin "1") (pinfunction "1_1") (pintype "passive"))
    )
    (net (code "34") (name "Net-(Q6-C)") (class "Default")
      (node (ref "Q1") (pin "G") (pinfunction "G_G") (pintype "passive"))
      (node (ref "Q6") (pin "3") (pinfunction "C_3") (pintype "passive"))
      (node (ref "R14") (pin "2") (pinfunction "2_2") (pintype "passive"))
      (node (ref "R15") (pin "1") (pinfunction "1_1") (pintype "passive"))
      (node (ref "R16") (pin "2") (pinfunction "2_2") (pintype "passive"))
    )
    (net (code "35") (name "Net-(RELAY-5)") (class "Default")
      (node (ref "HEATSINK") (pin "P$1") (pinfunction "P$1_P$1") (pintype "bidirectional"))
      (node (ref "Q1") (pin "D") (pinfunction "D_D") (pintype "passive"))
      (node (ref "RELAY") (pin "P$5") (pinfunction "5_P$5") (pintype "bidirectional"))
    )
    (net (code "36") (name "Net-(RL1-Pad2)") (class "Default")
      (node (ref "RL1") (pin "2") (pinfunction "2_2") (pintype "passive"))
      (node (ref "RL2") (pin "1") (pinfunction "1_1") (pintype "passive"))
    )
    (net (code "37") (name "unconnected-(ATX--12V-Pad14)") (class "Default")
      (node (ref "ATX") (pin "14") (pinfunction "-12V_14") (pintype "bidirectional"))
    )
    (net (code "38") (name "unconnected-(ATX-3V3_1-Pad1)") (class "Default")
      (node (ref "ATX") (pin "1") (pinfunction "3V3_1_1") (pintype "bidirectional"))
    )
    (net (code "39") (name "unconnected-(ATX-3V3_2-Pad2)") (class "Default")
      (node (ref "ATX") (pin "2") (pinfunction "3V3_2_2") (pintype "bidirectional"))
    )
    (net (code "40") (name "unconnected-(ATX-3V3_12-Pad12)") (class "Default")
      (node (ref "ATX") (pin "12") (pinfunction "3V3_12_12") (pintype "bidirectional"))
    )
    (net (code "41") (name "unconnected-(ATX-3V3_13-Pad13)") (class "Default")
      (node (ref "ATX") (pin "13") (pinfunction "3V3_13_13") (pintype "bidirectional"))
    )
    (net (code "42") (name "unconnected-(ATX-5V_4-Pad4)") (class "Default")
      (node (ref "ATX") (pin "4") (pinfunction "5V_4_4") (pintype "bidirectional"))
    )
    (net (code "43") (name "unconnected-(ATX-5V_6-Pad6)") (class "Default")
      (node (ref "ATX") (pin "6") (pinfunction "5V_6_6") (pintype "bidirectional"))
    )
    (net (code "44") (name "unconnected-(ATX-5V_21-Pad21)") (class "Default")
      (node (ref "ATX") (pin "21") (pinfunction "5V_21_21") (pintype "bidirectional"))
    )
    (net (code "45") (name "unconnected-(ATX-5V_22-Pad22)") (class "Default")
      (node (ref "ATX") (pin "22") (pinfunction "5V_22_22") (pintype "bidirectional"))
    )
    (net (code "46") (name "unconnected-(ATX-5V_23-Pad23)") (class "Default")
      (node (ref "ATX") (pin "23") (pinfunction "5V_23_23") (pintype "bidirectional"))
    )
    (net (code "47") (name "unconnected-(ATX-5V_STANDBY-Pad9)") (class "Default")
      (node (ref "ATX") (pin "9") (pinfunction "5V_STANDBY_9") (pintype "bidirectional"))
    )
    (net (code "48") (name "unconnected-(ATX-PWR_GOOD-Pad8)") (class "Default")
      (node (ref "ATX") (pin "8") (pinfunction "PWR_GOOD_8") (pintype "bidirectional"))
    )
    (net (code "49") (name "unconnected-(ATX-RESERVED-Pad20)") (class "Default")
      (node (ref "ATX") (pin "20") (pinfunction "RESERVED_20") (pintype "bidirectional"))
    )
    (net (code "50") (name "unconnected-(DIN4-PadP$5)") (class "Default")
      (node (ref "DIN4") (pin "P$5") (pinfunction "P$5_P$5") (pintype "bidirectional"))
    )
    (net (code "51") (name "unconnected-(ESP1-CS0-Pad9)") (class "Default")
      (node (ref "ESP1") (pin "9") (pinfunction "CS0_9") (pintype "bidirectional"))
    )
    (net (code "52") (name "unconnected-(ESP1-IO9-Pad11)") (class "Default")
      (node (ref "ESP1") (pin "11") (pinfunction "IO9_11") (pintype "bidirectional"))
    )
    (net (code "53") (name "unconnected-(ESP1-IO10-Pad12)") (class "Default")
      (node (ref "ESP1") (pin "12") (pinfunction "IO10_12") (pintype "bidirectional"))
    )
    (net (code "54") (name "unconnected-(ESP1-MISO-Pad10)") (class "Default")
      (node (ref "ESP1") (pin "10") (pinfunction "MISO_10") (pintype "bidirectional"))
    )
    (net (code "55") (name "unconnected-(ESP1-MOSI-Pad13)") (class "Default")
      (node (ref "ESP1") (pin "13") (pinfunction "MOSI_13") (pintype "bidirectional"))
    )
    (net (code "56") (name "unconnected-(ESP1-SCLK-Pad14)") (class "Default")
      (node (ref "ESP1") (pin "14") (pinfunction "SCLK_14") (pintype "bidirectional"))
    )
    (net (code "57") (name "unconnected-(FANA-S-Pad1)") (class "Default")
      (node (ref "FAN") (pin "1") (pinfunction "S_1") (pintype "passive"))
    )
    (net (code "58") (name "unconnected-(IC2-XIN-PadP$10)") (class "Default")
      (node (ref "IC2") (pin "P$10") (pinfunction "XIN_P$10") (pintype "bidirectional"))
    )
    (net (code "59") (name "unconnected-(IC2-XOUT-PadP$11)") (class "Default")
      (node (ref "IC2") (pin "P$11") (pinfunction "XOUT_P$11") (pintype "bidirectional"))
    )
    (net (code "60") (name "unconnected-(SERIAL4-Pad1)") (class "Default")
      (node (ref "SERIAL4") (pin "1") (pinfunction "1_1") (pintype "passive"))
    )
    (net (code "61") (name "unconnected-(SERIAL6-Pad1)") (class "Default")
      (node (ref "SERIAL6") (pin "1") (pinfunction "1_1") (pintype "passive"))
    )
    (net (code "62") (name "unconnected-(SERIAL6-Pad4)") (class "Default")
      (node (ref "SERIAL6") (pin "4") (pinfunction "4_4") (pintype "passive"))
    )
    (net (code "63") (name "unconnected-(SERIAL6-Pad5)") (class "Default")
      (node (ref "SERIAL6") (pin "5") (pinfunction "5_5") (pintype "passive"))
    )
  )
)
